# Sensor_PCB.net
KiCad netlist of a schematic drawn in EAGLE
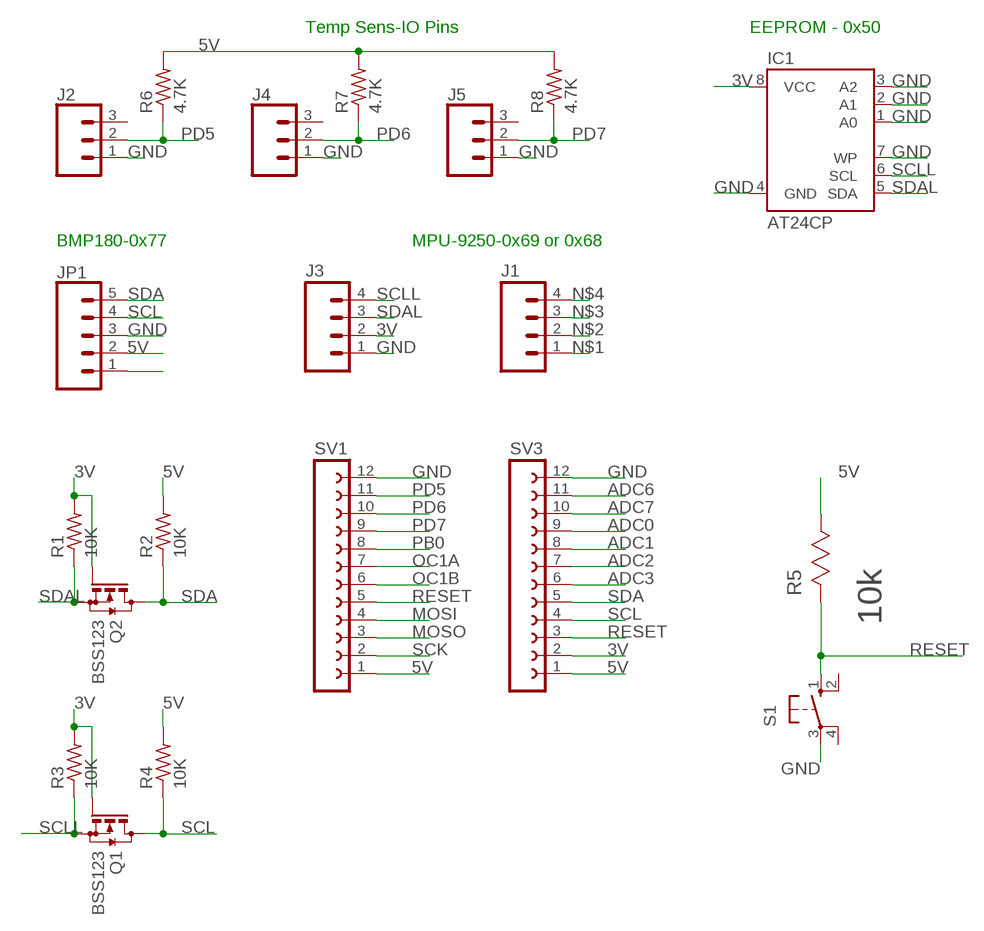
[diagram p0: schematic, sheet 1]

(export (version "E")
  (design (tool "Eeschema 10.0.6"))
  (components
    (comp (ref "IC1")
      (value "AT24CP")
      (footprint "eagle-import:DIL08")
      (fields (field (name "MPN") "AT24C1024BW-SH-B"))
      (libsource (lib "eagle-import") (part "AT24CP"))
    )
    (comp (ref "J1")
      (value "M04PTH")
      (footprint "eagle-import:1X04")
      (libsource (lib "eagle-import") (part "M04PTH"))
    )
    (comp (ref "J2")
      (value "CONN_03")
      (footprint "eagle-import:1X03")
      (libsource (lib "eagle-import") (part "CONN_03"))
    )
    (comp (ref "J3")
      (value "M04PTH")
      (footprint "eagle-import:1X04")
      (libsource (lib "eagle-import") (part "M04PTH"))
    )
    (comp (ref "J4")
      (value "CONN_03")
      (footprint "eagle-import:1X03")
      (libsource (lib "eagle-import") (part "CONN_03"))
    )
    (comp (ref "J5")
      (value "CONN_03")
      (footprint "eagle-import:1X03")
      (libsource (lib "eagle-import") (part "CONN_03"))
    )
    (comp (ref "JP1")
      (value "CONN_05")
      (footprint "eagle-import:1X05")
      (libsource (lib "eagle-import") (part "CONN_05"))
    )
    (comp (ref "Q1")
      (value "BSS123")
      (footprint "eagle-import:SOT23")
      (libsource (lib "eagle-import") (part "BSS123"))
    )
    (comp (ref "Q2")
      (value "BSS123")
      (footprint "eagle-import:SOT23")
      (libsource (lib "eagle-import") (part "BSS123"))
    )
    (comp (ref "R1")
      (value "10K")
      (footprint "eagle-import:M1406")
      (libsource (lib "eagle-import") (part "R-US_M1406"))
    )
    (comp (ref "R2")
      (value "10K")
      (footprint "eagle-import:M1406")
      (libsource (lib "eagle-import") (part "R-US_M1406"))
    )
    (comp (ref "R3")
      (value "10K")
      (footprint "eagle-import:M1406")
      (libsource (lib "eagle-import") (part "R-US_M1406"))
    )
    (comp (ref "R4")
      (value "10K")
      (footprint "eagle-import:M1406")
      (libsource (lib "eagle-import") (part "R-US_M1406"))
    )
    (comp (ref "R5")
      (value "10k")
      (footprint "eagle-import:RESC2013X65N")
      (fields (field (name "MPN") "CRCW08051M00JNEA") (field (name "TOLERANCE") "± 5.0 %"))
      (libsource (lib "eagle-import") (part "CRCW08051M00JNEA"))
    )
    (comp (ref "R6")
      (value "4.7K")
      (footprint "eagle-import:M1406")
      (libsource (lib "eagle-import") (part "R-US_M1406"))
    )
    (comp (ref "R7")
      (value "4.7K")
      (footprint "eagle-import:M1406")
      (libsource (lib "eagle-import") (part "R-US_M1406"))
    )
    (comp (ref "R8")
      (value "4.7K")
      (footprint "eagle-import:M1406")
      (libsource (lib "eagle-import") (part "R-US_M1406"))
    )
    (comp (ref "S1")
      (value "10-XX")
      (footprint "eagle-import:B3F-10XX")
      (fields (field (name "MPN") "B3F-1000"))
      (libsource (lib "eagle-import") (part "10-XX"))
    )
    (comp (ref "SV1")
      (value "FE12-1")
      (footprint "eagle-import:FE12")
      (libsource (lib "eagle-import") (part "FE12-1"))
    )
    (comp (ref "SV3")
      (value "FE12-1")
      (footprint "eagle-import:FE12")
      (libsource (lib "eagle-import") (part "FE12-1"))
    )
  )
  (nets
    (net (code "1") (name "/3V") (class "Default")
      (node (ref "IC1") (pin "8") (pinfunction "VCC_8") (pintype "power_in"))
      (node (ref "J3") (pin "2") (pinfunction "2_2") (pintype "passive"))
      (node (ref "Q1") (pin "1") (pinfunction "G_1") (pintype "passive"))
      (node (ref "Q2") (pin "1") (pinfunction "G_1") (pintype "passive"))
      (node (ref "R1") (pin "2") (pinfunction "2_2") (pintype "passive"))
      (node (ref "R3") (pin "2") (pinfunction "2_2") (pintype "passive"))
      (node (ref "SV3") (pin "2") (pinfunction "2_2") (pintype "passive"))
    )
    (net (code "2") (name "/5V") (class "Default")
      (node (ref "JP1") (pin "2") (pinfunction "2_2") (pintype "passive"))
      (node (ref "R2") (pin "2") (pinfunction "2_2") (pintype "passive"))
      (node (ref "R4") (pin "2") (pinfunction "2_2") (pintype "passive"))
      (node (ref "R5") (pin "1") (pinfunction "1_1") (pintype "passive"))
      (node (ref "R6") (pin "2") (pinfunction "2_2") (pintype "passive"))
      (node (ref "R7") (pin "2") (pinfunction "2_2") (pintype "passive"))
      (node (ref "R8") (pin "2") (pinfunction "2_2") (pintype "passive"))
      (node (ref "SV1") (pin "1") (pinfunction "1_1") (pintype "passive"))
      (node (ref "SV3") (pin "1") (pinfunction "1_1") (pintype "passive"))
    )
    (net (code "3") (name "/ADC0") (class "Default")
      (node (ref "SV3") (pin "9") (pinfunction "9_9") (pintype "passive"))
    )
    (net (code "4") (name "/ADC1") (class "Default")
      (node (ref "SV3") (pin "8") (pinfunction "8_8") (pintype "passive"))
    )
    (net (code "5") (name "/ADC2") (class "Default")
      (node (ref "SV3") (pin "7") (pinfunction "7_7") (pintype "passive"))
    )
    (net (code "6") (name "/ADC3") (class "Default")
      (node (ref "SV3") (pin "6") (pinfunction "6_6") (pintype "passive"))
    )
    (net (code "7") (name "/ADC6") (class "Default")
      (node (ref "SV3") (pin "11") (pinfunction "11_11") (pintype "passive"))
    )
    (net (code "8") (name "/ADC7") (class "Default")
      (node (ref "SV3") (pin "10") (pinfunction "10_10") (pintype "passive"))
    )
    (net (code "9") (name "/GND") (class "Default")
      (node (ref "IC1") (pin "1") (pinfunction "A0_1") (pintype "input"))
      (node (ref "IC1") (pin "2") (pinfunction "A1_2") (pintype "input"))
      (node (ref "IC1") (pin "3") (pinfunction "A2_3") (pintype "input"))
      (node (ref "IC1") (pin "4") (pinfunction "GND_4") (pintype "power_in"))
      (node (ref "IC1") (pin "7") (pinfunction "WP_7") (pintype "input"))
      (node (ref "J2") (pin "1") (pinfunction "1_1") (pintype "passive"))
      (node (ref "J3") (pin "1") (pinfunction "1_1") (pintype "passive"))
      (node (ref "J4") (pin "1") (pinfunction "1_1") (pintype "passive"))
      (node (ref "J5") (pin "1") (pinfunction "1_1") (pintype "passive"))
      (node (ref "JP1") (pin "3") (pinfunction "3_3") (pintype "passive"))
      (node (ref "S1") (pin "3") (pinfunction "P_3") (pintype "passive"))
      (node (ref "SV1") (pin "12") (pinfunction "12_12") (pintype "passive"))
      (node (ref "SV3") (pin "12") (pinfunction "12_12") (pintype "passive"))
    )
    (net (code "10") (name "/MOSI") (class "Default")
      (node (ref "SV1") (pin "4") (pinfunction "4_4") (pintype "passive"))
    )
    (net (code "11") (name "/MOSO") (class "Default")
      (node (ref "SV1") (pin "3") (pinfunction "3_3") (pintype "passive"))
    )
    (net (code "12") (name "/N$1") (class "Default")
      (node (ref "J1") (pin "1") (pinfunction "1_1") (pintype "passive"))
    )
    (net (code "13") (name "/N$2") (class "Default")
      (node (ref "J1") (pin "2") (pinfunction "2_2") (pintype "passive"))
    )
    (net (code "14") (name "/N$3") (class "Default")
      (node (ref "J1") (pin "3") (pinfunction "3_3") (pintype "passive"))
    )
    (net (code "15") (name "/N$4") (class "Default")
      (node (ref "J1") (pin "4") (pinfunction "4_4") (pintype "passive"))
    )
    (net (code "16") (name "/OC1A") (class "Default")
      (node (ref "SV1") (pin "7") (pinfunction "7_7") (pintype "passive"))
    )
    (net (code "17") (name "/OC1B") (class "Default")
      (node (ref "SV1") (pin "6") (pinfunction "6_6") (pintype "passive"))
    )
    (net (code "18") (name "/PB0") (class "Default")
      (node (ref "SV1") (pin "8") (pinfunction "8_8") (pintype "passive"))
    )
    (net (code "19") (name "/PD5") (class "Default")
      (node (ref "J2") (pin "2") (pinfunction "2_2") (pintype "passive"))
      (node (ref "R6") (pin "1") (pinfunction "1_1") (pintype "passive"))
      (node (ref "SV1") (pin "11") (pinfunction "11_11") (pintype "passive"))
    )
    (net (code "20") (name "/PD6") (class "Default")
      (node (ref "J4") (pin "2") (pinfunction "2_2") (pintype "passive"))
      (node (ref "R7") (pin "1") (pinfunction "1_1") (pintype "passive"))
      (node (ref "SV1") (pin "10") (pinfunction "10_10") (pintype "passive"))
    )
    (net (code "21") (name "/PD7") (class "Default")
      (node (ref "J5") (pin "2") (pinfunction "2_2") (pintype "passive"))
      (node (ref "R8") (pin "1") (pinfunction "1_1") (pintype "passive"))
      (node (ref "SV1") (pin "9") (pinfunction "9_9") (pintype "passive"))
    )
    (net (code "22") (name "/RESET") (class "Default")
      (node (ref "R5") (pin "2") (pinfunction "2_2") (pintype "passive"))
      (node (ref "S1") (pin "1") (pinfunction "S_1") (pintype "passive"))
      (node (ref "SV1") (pin "5") (pinfunction "5_5") (pintype "passive"))
      (node (ref "SV3") (pin "3") (pinfunction "3_3") (pintype "passive"))
    )
    (net (code "23") (name "/SCK") (class "Default")
      (node (ref "SV1") (pin "2") (pinfunction "2_2") (pintype "passive"))
    )
    (net (code "24") (name "/SCL") (class "Default")
      (node (ref "JP1") (pin "4") (pinfunction "4_4") (pintype "passive"))
      (node (ref "Q1") (pin "3") (pinfunction "D_3") (pintype "passive"))
      (node (ref "R4") (pin "1") (pinfunction "1_1") (pintype "passive"))
      (node (ref "SV3") (pin "4") (pinfunction "4_4") (pintype "passive"))
    )
    (net (code "25") (name "/SCLL") (class "Default")
      (node (ref "IC1") (pin "6") (pinfunction "SCL_6") (pintype "bidirectional"))
      (node (ref "J3") (pin "4") (pinfunction "4_4") (pintype "passive"))
      (node (ref "Q1") (pin "2") (pinfunction "S_2") (pintype "passive"))
      (node (ref "R3") (pin "1") (pinfunction "1_1") (pintype "passive"))
    )
    (net (code "26") (name "/SDA") (class "Default")
      (node (ref "JP1") (pin "5") (pinfunction "5_5") (pintype "passive"))
      (node (ref "Q2") (pin "3") (pinfunction "D_3") (pintype "passive"))
      (node (ref "R2") (pin "1") (pinfunction "1_1") (pintype "passive"))
      (node (ref "SV3") (pin "5") (pinfunction "5_5") (pintype "passive"))
    )
    (net (code "27") (name "/SDAL") (class "Default")
      (node (ref "IC1") (pin "5") (pinfunction "SDA_5") (pintype "bidirectional"))
      (node (ref "J3") (pin "3") (pinfunction "3_3") (pintype "passive"))
      (node (ref "Q2") (pin "2") (pinfunction "S_2") (pintype "passive"))
      (node (ref "R1") (pin "1") (pinfunction "1_1") (pintype "passive"))
    )
    (net (code "28") (name "unconnected-(J2-Pad3)") (class "Default")
      (node (ref "J2") (pin "3") (pinfunction "3_3") (pintype "passive"))
    )
    (net (code "29") (name "unconnected-(J4-Pad3)") (class "Default")
      (node (ref "J4") (pin "3") (pinfunction "3_3") (pintype "passive"))
    )
    (net (code "30") (name "unconnected-(J5-Pad3)") (class "Default")
      (node (ref "J5") (pin "3") (pinfunction "3_3") (pintype "passive"))
    )
    (net (code "31") (name "unconnected-(JP1-Pad1)") (class "Default")
      (node (ref "JP1") (pin "1") (pinfunction "1_1") (pintype "passive"))
    )
    (net (code "32") (name "unconnected-(S1-P1-Pad4)") (class "Default")
      (node (ref "S1") (pin "4") (pinfunction "P1_4") (pintype "passive"))
    )
    (net (code "33") (name "unconnected-(S1-S1-Pad2)") (class "Default")
      (node (ref "S1") (pin "2") (pinfunction "S1_2") (pintype "passive"))
    )
  )
)
